# 40_pin_adapter.net
KiCad netlist of a schematic drawn in EAGLE
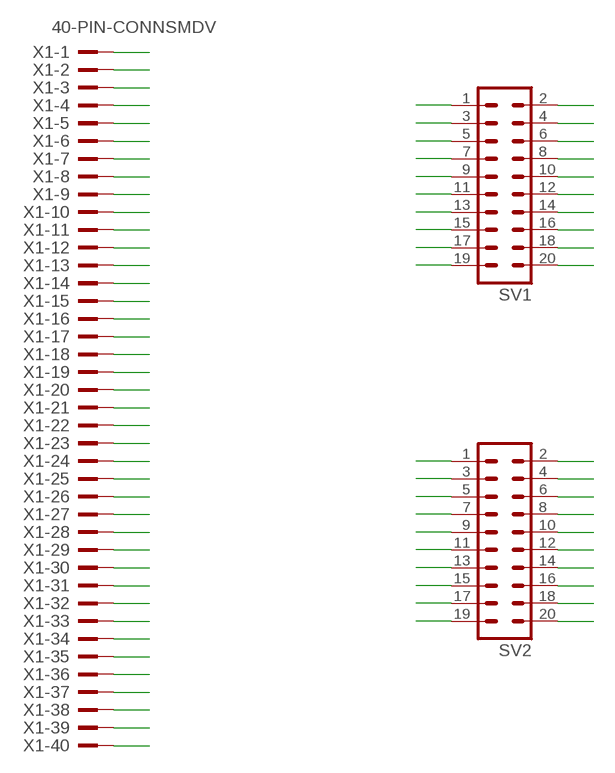
[diagram p0: schematic, sheet 1]

(export (version "E")
  (design (tool "Eeschema 10.0.6"))
  (components
    (comp (ref "SV1")
      (value "MA10-2")
      (footprint "eagle-import:MA10-2")
      (libsource (lib "eagle-import") (part "MA10-2"))
    )
    (comp (ref "SV2")
      (value "MA10-2")
      (footprint "eagle-import:MA10-2")
      (libsource (lib "eagle-import") (part "MA10-2"))
    )
    (comp (ref "X1")
      (value "40-PIN-CONNSMDV")
      (footprint "eagle-import:SMD")
      (libsource (lib "eagle-import") (part "40-PIN-CONNSMDV"))
    )
  )
  (nets
    (net (code "1") (name "/1") (class "Default")
      (node (ref "SV1") (pin "1") (pinfunction "1_1") (pintype "passive"))
      (node (ref "X1") (pin "1") (pinfunction "KL_1") (pintype "passive"))
    )
    (net (code "2") (name "/2") (class "Default")
      (node (ref "SV1") (pin "2") (pinfunction "2_2") (pintype "passive"))
      (node (ref "X1") (pin "2") (pinfunction "KL_2") (pintype "passive"))
    )
    (net (code "3") (name "/3") (class "Default")
      (node (ref "SV1") (pin "3") (pinfunction "3_3") (pintype "passive"))
      (node (ref "X1") (pin "3") (pinfunction "KL_3") (pintype "passive"))
    )
    (net (code "4") (name "/4") (class "Default")
      (node (ref "SV1") (pin "4") (pinfunction "4_4") (pintype "passive"))
      (node (ref "X1") (pin "4") (pinfunction "KL_4") (pintype "passive"))
    )
    (net (code "5") (name "/5") (class "Default")
      (node (ref "SV1") (pin "5") (pinfunction "5_5") (pintype "passive"))
      (node (ref "X1") (pin "5") (pinfunction "KL_5") (pintype "passive"))
    )
    (net (code "6") (name "/6") (class "Default")
      (node (ref "SV1") (pin "6") (pinfunction "6_6") (pintype "passive"))
      (node (ref "X1") (pin "6") (pinfunction "KL_6") (pintype "passive"))
    )
    (net (code "7") (name "/7") (class "Default")
      (node (ref "SV1") (pin "7") (pinfunction "7_7") (pintype "passive"))
      (node (ref "X1") (pin "7") (pinfunction "KL_7") (pintype "passive"))
    )
    (net (code "8") (name "/8") (class "Default")
      (node (ref "SV1") (pin "8") (pinfunction "8_8") (pintype "passive"))
      (node (ref "X1") (pin "8") (pinfunction "KL_8") (pintype "passive"))
    )
    (net (code "9") (name "/9") (class "Default")
      (node (ref "SV1") (pin "9") (pinfunction "9_9") (pintype "passive"))
      (node (ref "X1") (pin "9") (pinfunction "KL_9") (pintype "passive"))
    )
    (net (code "10") (name "/10") (class "Default")
      (node (ref "SV1") (pin "10") (pinfunction "10_10") (pintype "passive"))
      (node (ref "X1") (pin "10") (pinfunction "KL_10") (pintype "passive"))
    )
    (net (code "11") (name "/11") (class "Default")
      (node (ref "SV1") (pin "11") (pinfunction "11_11") (pintype "passive"))
      (node (ref "X1") (pin "11") (pinfunction "KL_11") (pintype "passive"))
    )
    (net (code "12") (name "/12") (class "Default")
      (node (ref "SV1") (pin "12") (pinfunction "12_12") (pintype "passive"))
      (node (ref "X1") (pin "12") (pinfunction "KL_12") (pintype "passive"))
    )
    (net (code "13") (name "/13") (class "Default")
      (node (ref "SV1") (pin "13") (pinfunction "13_13") (pintype "passive"))
      (node (ref "X1") (pin "13") (pinfunction "KL_13") (pintype "passive"))
    )
    (net (code "14") (name "/14") (class "Default")
      (node (ref "SV1") (pin "14") (pinfunction "14_14") (pintype "passive"))
      (node (ref "X1") (pin "14") (pinfunction "KL_14") (pintype "passive"))
    )
    (net (code "15") (name "/15") (class "Default")
      (node (ref "SV1") (pin "15") (pinfunction "15_15") (pintype "passive"))
      (node (ref "X1") (pin "15") (pinfunction "KL_15") (pintype "passive"))
    )
    (net (code "16") (name "/16") (class "Default")
      (node (ref "SV1") (pin "16") (pinfunction "16_16") (pintype "passive"))
      (node (ref "X1") (pin "16") (pinfunction "KL_16") (pintype "passive"))
    )
    (net (code "17") (name "/17") (class "Default")
      (node (ref "SV1") (pin "17") (pinfunction "17_17") (pintype "passive"))
      (node (ref "X1") (pin "17") (pinfunction "KL_17") (pintype "passive"))
    )
    (net (code "18") (name "/18") (class "Default")
      (node (ref "SV1") (pin "18") (pinfunction "18_18") (pintype "passive"))
      (node (ref "X1") (pin "18") (pinfunction "KL_18") (pintype "passive"))
    )
    (net (code "19") (name "/19") (class "Default")
      (node (ref "SV1") (pin "19") (pinfunction "19_19") (pintype "passive"))
      (node (ref "X1") (pin "19") (pinfunction "KL_19") (pintype "passive"))
    )
    (net (code "20") (name "/20") (class "Default")
      (node (ref "SV1") (pin "20") (pinfunction "20_20") (pintype "passive"))
      (node (ref "X1") (pin "20") (pinfunction "KL_20") (pintype "passive"))
    )
    (net (code "21") (name "/21") (class "Default")
      (node (ref "SV2") (pin "1") (pinfunction "1_1") (pintype "passive"))
      (node (ref "X1") (pin "21") (pinfunction "KL_21") (pintype "passive"))
    )
    (net (code "22") (name "/22") (class "Default")
      (node (ref "SV2") (pin "2") (pinfunction "2_2") (pintype "passive"))
      (node (ref "X1") (pin "22") (pinfunction "KL_22") (pintype "passive"))
    )
    (net (code "23") (name "/23") (class "Default")
      (node (ref "SV2") (pin "3") (pinfunction "3_3") (pintype "passive"))
      (node (ref "X1") (pin "23") (pinfunction "KL_23") (pintype "passive"))
    )
    (net (code "24") (name "/24") (class "Default")
      (node (ref "SV2") (pin "4") (pinfunction "4_4") (pintype "passive"))
      (node (ref "X1") (pin "24") (pinfunction "KL_24") (pintype "passive"))
    )
    (net (code "25") (name "/25") (class "Default")
      (node (ref "SV2") (pin "5") (pinfunction "5_5") (pintype "passive"))
      (node (ref "X1") (pin "25") (pinfunction "KL_25") (pintype "passive"))
    )
    (net (code "26") (name "/26") (class "Default")
      (node (ref "SV2") (pin "6") (pinfunction "6_6") (pintype "passive"))
      (node (ref "X1") (pin "26") (pinfunction "KL_26") (pintype "passive"))
    )
    (net (code "27") (name "/27") (class "Default")
      (node (ref "SV2") (pin "7") (pinfunction "7_7") (pintype "passive"))
      (node (ref "X1") (pin "27") (pinfunction "KL_27") (pintype "passive"))
    )
    (net (code "28") (name "/28") (class "Default")
      (node (ref "SV2") (pin "8") (pinfunction "8_8") (pintype "passive"))
      (node (ref "X1") (pin "28") (pinfunction "KL_28") (pintype "passive"))
    )
    (net (code "29") (name "/29") (class "Default")
      (node (ref "SV2") (pin "9") (pinfunction "9_9") (pintype "passive"))
      (node (ref "X1") (pin "29") (pinfunction "KL_29") (pintype "passive"))
    )
    (net (code "30") (name "/30") (class "Default")
      (node (ref "SV2") (pin "10") (pinfunction "10_10") (pintype "passive"))
      (node (ref "X1") (pin "30") (pinfunction "KL_30") (pintype "passive"))
    )
    (net (code "31") (name "/31") (class "Default")
      (node (ref "SV2") (pin "11") (pinfunction "11_11") (pintype "passive"))
      (node (ref "X1") (pin "31") (pinfunction "KL_31") (pintype "passive"))
    )
    (net (code "32") (name "/32") (class "Default")
      (node (ref "SV2") (pin "12") (pinfunction "12_12") (pintype "passive"))
      (node (ref "X1") (pin "32") (pinfunction "KL_32") (pintype "passive"))
    )
    (net (code "33") (name "/33") (class "Default")
      (node (ref "SV2") (pin "13") (pinfunction "13_13") (pintype "passive"))
      (node (ref "X1") (pin "33") (pinfunction "KL_33") (pintype "passive"))
    )
    (net (code "34") (name "/34") (class "Default")
      (node (ref "SV2") (pin "14") (pinfunction "14_14") (pintype "passive"))
      (node (ref "X1") (pin "34") (pinfunction "KL_34") (pintype "passive"))
    )
    (net (code "35") (name "/35") (class "Default")
      (node (ref "SV2") (pin "15") (pinfunction "15_15") (pintype "passive"))
      (node (ref "X1") (pin "35") (pinfunction "KL_35") (pintype "passive"))
    )
    (net (code "36") (name "/36") (class "Default")
      (node (ref "SV2") (pin "16") (pinfunction "16_16") (pintype "passive"))
      (node (ref "X1") (pin "36") (pinfunction "KL_36") (pintype "passive"))
    )
    (net (code "37") (name "/37") (class "Default")
      (node (ref "SV2") (pin "17") (pinfunction "17_17") (pintype "passive"))
      (node (ref "X1") (pin "37") (pinfunction "KL_37") (pintype "passive"))
    )
    (net (code "38") (name "/38") (class "Default")
      (node (ref "SV2") (pin "18") (pinfunction "18_18") (pintype "passive"))
      (node (ref "X1") (pin "38") (pinfunction "KL_38") (pintype "passive"))
    )
    (net (code "39") (name "/39") (class "Default")
      (node (ref "SV2") (pin "19") (pinfunction "19_19") (pintype "passive"))
      (node (ref "X1") (pin "39") (pinfunction "KL_39") (pintype "passive"))
    )
    (net (code "40") (name "/40") (class "Default")
      (node (ref "SV2") (pin "20") (pinfunction "20_20") (pintype "passive"))
      (node (ref "X1") (pin "40") (pinfunction "KL_40") (pintype "passive"))
    )
  )
)
